# LPF-400kHz-OPA820-THT.net
KiCad netlist of a schematic drawn in Altium Designer
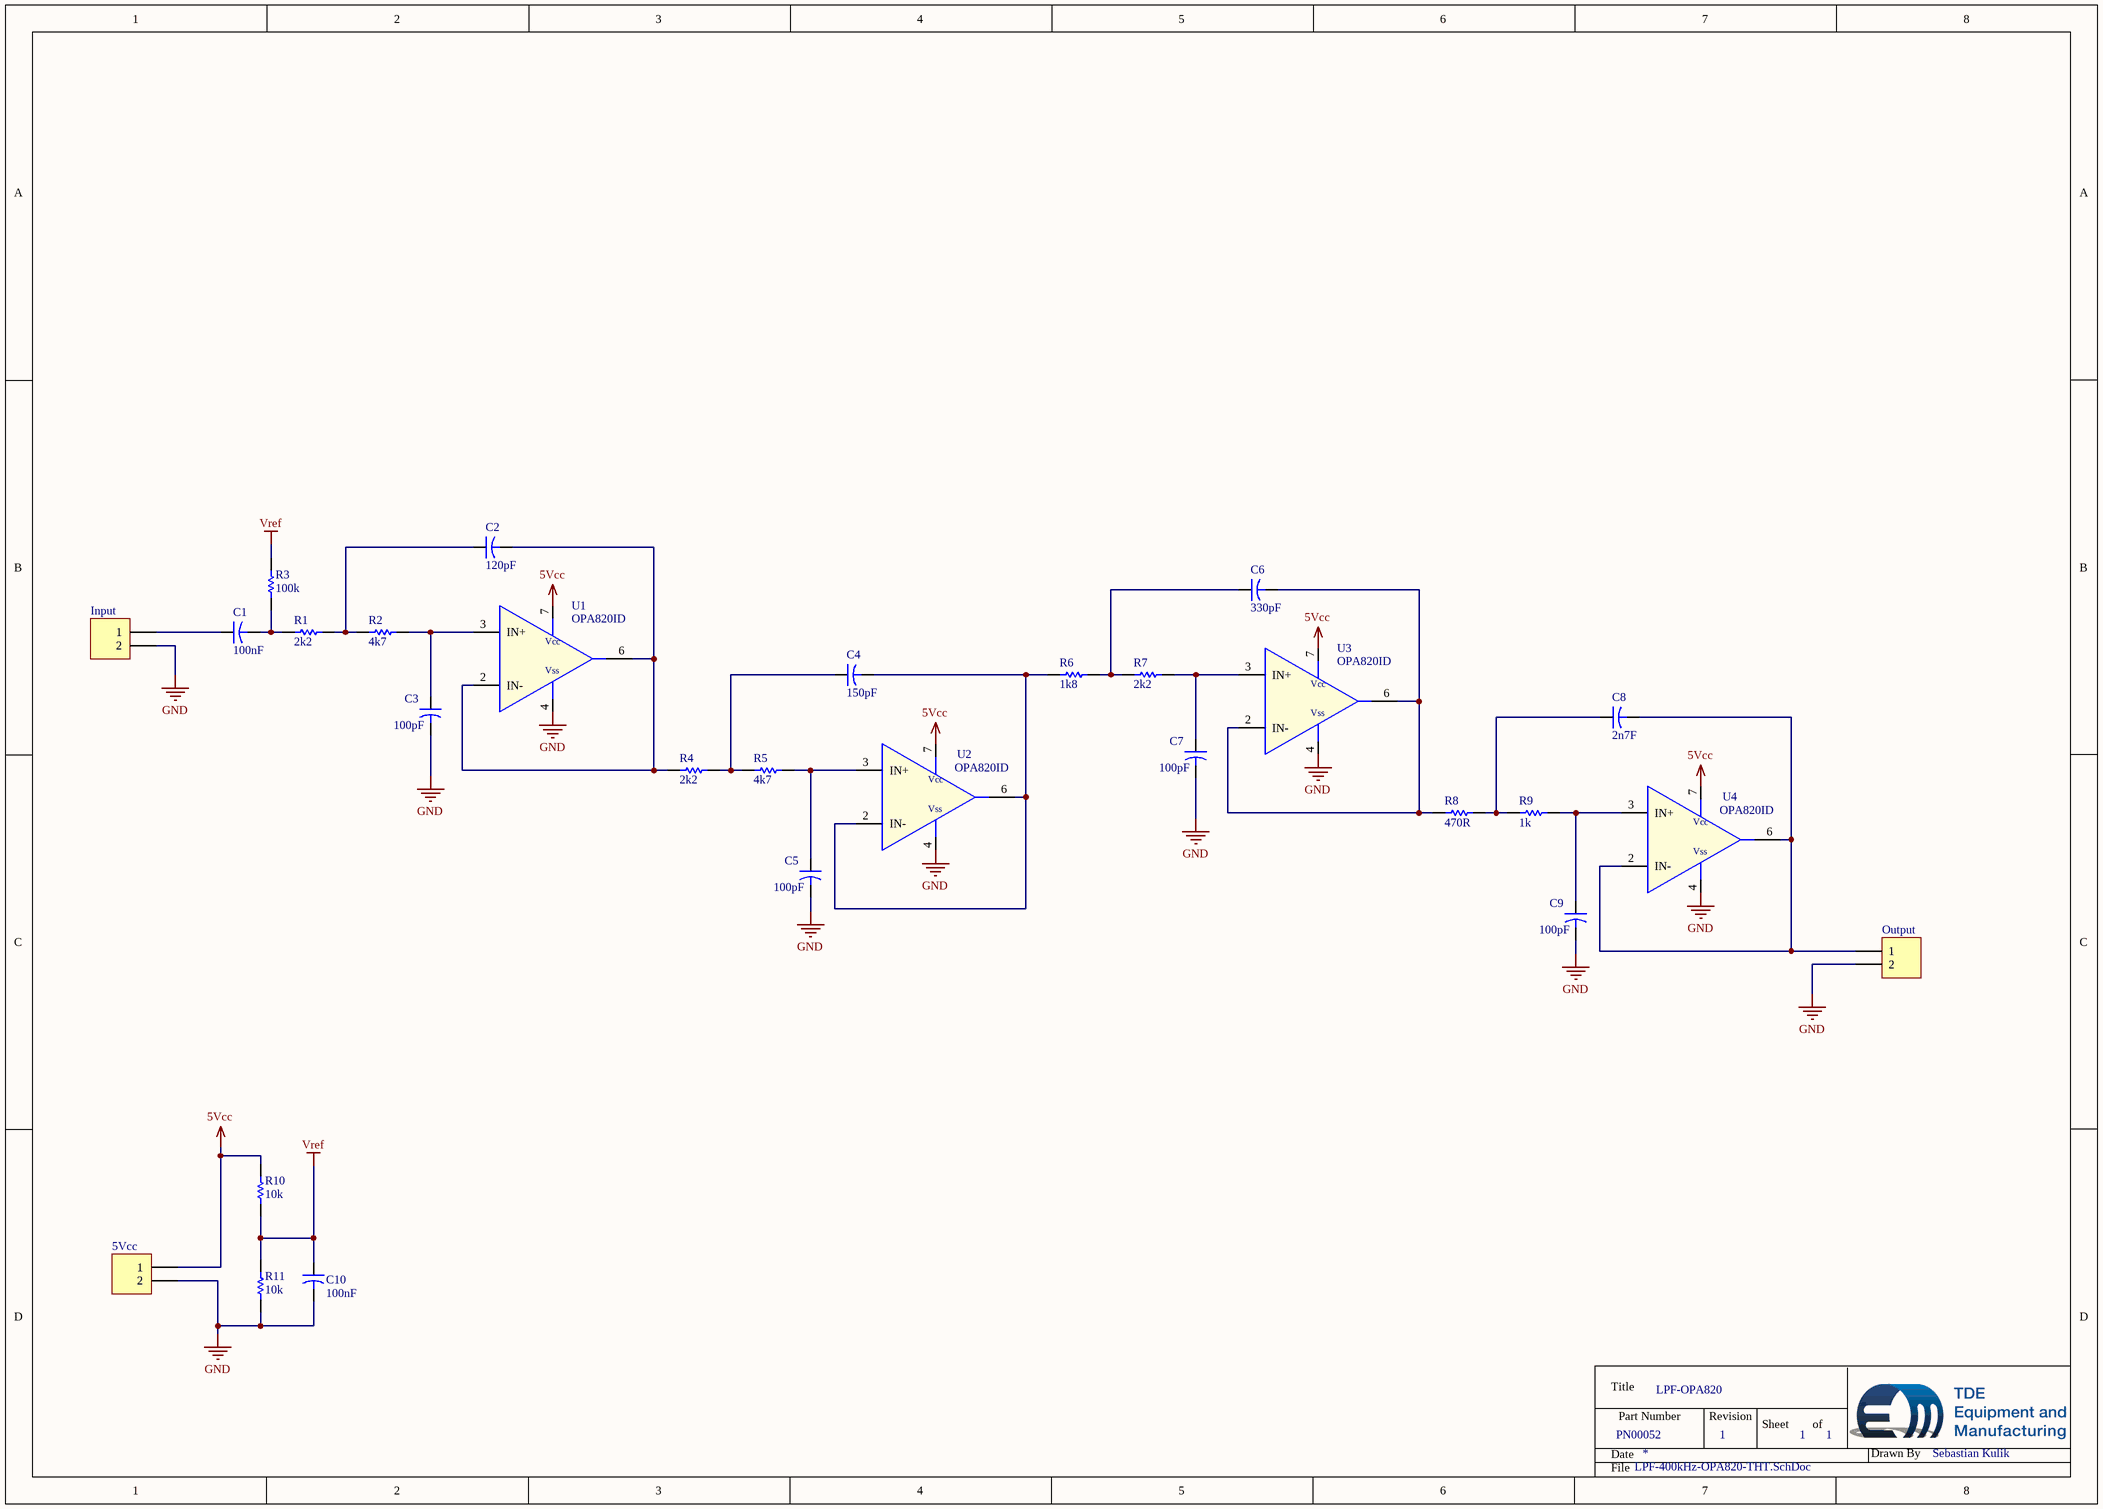
[diagram p0: LPF-400kHz-OPA820-THT.SchDoc]

(export (version "E")
  (design (tool "Eeschema 10.0.6"))
  (components
    (comp (ref "5Vcc")
      (value "PHOENIX_1715721")
      (footprint "Phoenix-2-5_08")
      (description "Phoenix, 2 pol, 5.08mm, 22A, 715721")
      (fields (field (name "MANUFACTURER") "Phoenix") (field (name "PUBLISHER") "Sebastian Kulik"))
      (libsource (lib "Connectors") (part "2Pol_1715721"))
    )
    (comp (ref "C1")
      (value "100nF")
      (footprint "Dummy-10mm")
      (description "Capacitor-Dummy-THT")
      (fields (field (name "PUBLISHER") "Sebastian Kulik"))
      (libsource (lib "Capacitors") (part "Capacitor-Dummy-THT"))
    )
    (comp (ref "C2")
      (value "120pF")
      (footprint "Dummy-10mm")
      (description "Capacitor-Dummy-THT")
      (fields (field (name "PUBLISHER") "Sebastian Kulik"))
      (libsource (lib "Capacitors") (part "Capacitor-Dummy-THT"))
    )
    (comp (ref "C3")
      (value "100pF")
      (footprint "Dummy-10mm")
      (description "Capacitor-Dummy-THT")
      (fields (field (name "PUBLISHER") "Sebastian Kulik"))
      (libsource (lib "Capacitors") (part "Capacitor-Dummy-THT"))
    )
    (comp (ref "C4")
      (value "150pF")
      (footprint "Dummy-10mm")
      (description "Capacitor-Dummy-THT")
      (fields (field (name "PUBLISHER") "Sebastian Kulik"))
      (libsource (lib "Capacitors") (part "Capacitor-Dummy-THT"))
    )
    (comp (ref "C5")
      (value "100pF")
      (footprint "Dummy-10mm")
      (description "Capacitor-Dummy-THT")
      (fields (field (name "PUBLISHER") "Sebastian Kulik"))
      (libsource (lib "Capacitors") (part "Capacitor-Dummy-THT"))
    )
    (comp (ref "C6")
      (value "330pF")
      (footprint "Dummy-10mm")
      (description "Capacitor-Dummy-THT")
      (fields (field (name "PUBLISHER") "Sebastian Kulik"))
      (libsource (lib "Capacitors") (part "Capacitor-Dummy-THT"))
    )
    (comp (ref "C7")
      (value "100pF")
      (footprint "Dummy-10mm")
      (description "Capacitor-Dummy-THT")
      (fields (field (name "PUBLISHER") "Sebastian Kulik"))
      (libsource (lib "Capacitors") (part "Capacitor-Dummy-THT"))
    )
    (comp (ref "C8")
      (value "2n7F")
      (footprint "Dummy-10mm")
      (description "Capacitor-Dummy-THT")
      (fields (field (name "PUBLISHER") "Sebastian Kulik"))
      (libsource (lib "Capacitors") (part "Capacitor-Dummy-THT"))
    )
    (comp (ref "C9")
      (value "100pF")
      (footprint "Dummy-10mm")
      (description "Capacitor-Dummy-THT")
      (fields (field (name "PUBLISHER") "Sebastian Kulik"))
      (libsource (lib "Capacitors") (part "Capacitor-Dummy-THT"))
    )
    (comp (ref "C10")
      (value "100nF")
      (footprint "Dummy-10mm")
      (description "Capacitor-Dummy-THT")
      (fields (field (name "PUBLISHER") "Sebastian Kulik"))
      (libsource (lib "Capacitors") (part "Capacitor-Dummy-THT"))
    )
    (comp (ref "Input")
      (value "PHOENIX_1715721")
      (footprint "Phoenix-2-5_08")
      (description "Phoenix, 2 pol, 5.08mm, 22A, 715721")
      (fields (field (name "MANUFACTURER") "Phoenix") (field (name "PUBLISHER") "Sebastian Kulik"))
      (libsource (lib "Connectors") (part "2Pol_1715721"))
    )
    (comp (ref "Output")
      (value "PHOENIX_1715721")
      (footprint "Phoenix-2-5_08")
      (description "Phoenix, 2 pol, 5.08mm, 22A, 715721")
      (fields (field (name "MANUFACTURER") "Phoenix") (field (name "PUBLISHER") "Sebastian Kulik"))
      (libsource (lib "") (part "2Pol_1715721_1"))
    )
    (comp (ref "R1")
      (value "2k2")
      (footprint "Dummy-10mm")
      (description "Resistor-Dummy-THT")
      (fields (field (name "PUBLISHER") "Sebastian Kulik"))
      (libsource (lib "Resistors") (part "Resistor-Dummy-THT"))
    )
    (comp (ref "R2")
      (value "4k7")
      (footprint "Dummy-10mm")
      (description "Resistor-Dummy-THT")
      (fields (field (name "PUBLISHER") "Sebastian Kulik"))
      (libsource (lib "Resistors") (part "Resistor-Dummy-THT"))
    )
    (comp (ref "R3")
      (value "100k")
      (footprint "Dummy-10mm")
      (description "Resistor-Dummy-THT")
      (fields (field (name "PUBLISHER") "Sebastian Kulik"))
      (libsource (lib "Resistors") (part "Resistor-Dummy-THT"))
    )
    (comp (ref "R4")
      (value "2k2")
      (footprint "Dummy-10mm")
      (description "Resistor-Dummy-THT")
      (fields (field (name "PUBLISHER") "Sebastian Kulik"))
      (libsource (lib "Resistors") (part "Resistor-Dummy-THT"))
    )
    (comp (ref "R5")
      (value "4k7")
      (footprint "Dummy-10mm")
      (description "Resistor-Dummy-THT")
      (fields (field (name "PUBLISHER") "Sebastian Kulik"))
      (libsource (lib "Resistors") (part "Resistor-Dummy-THT"))
    )
    (comp (ref "R6")
      (value "1k8")
      (footprint "Dummy-10mm")
      (description "Resistor-Dummy-THT")
      (fields (field (name "PUBLISHER") "Sebastian Kulik"))
      (libsource (lib "Resistors") (part "Resistor-Dummy-THT"))
    )
    (comp (ref "R7")
      (value "2k2")
      (footprint "Dummy-10mm")
      (description "Resistor-Dummy-THT")
      (fields (field (name "PUBLISHER") "Sebastian Kulik"))
      (libsource (lib "Resistors") (part "Resistor-Dummy-THT"))
    )
    (comp (ref "R8")
      (value "470R")
      (footprint "Dummy-10mm")
      (description "Resistor-Dummy-THT")
      (fields (field (name "PUBLISHER") "Sebastian Kulik"))
      (libsource (lib "Resistors") (part "Resistor-Dummy-THT"))
    )
    (comp (ref "R9")
      (value "1k")
      (footprint "Dummy-10mm")
      (description "Resistor-Dummy-THT")
      (fields (field (name "PUBLISHER") "Sebastian Kulik"))
      (libsource (lib "Resistors") (part "Resistor-Dummy-THT"))
    )
    (comp (ref "R10")
      (value "10k")
      (footprint "Dummy-10mm")
      (description "Resistor-Dummy-THT")
      (fields (field (name "PUBLISHER") "Sebastian Kulik"))
      (libsource (lib "Resistors") (part "Resistor-Dummy-THT"))
    )
    (comp (ref "R11")
      (value "10k")
      (footprint "Dummy-10mm")
      (description "Resistor-Dummy-THT")
      (fields (field (name "PUBLISHER") "Sebastian Kulik"))
      (libsource (lib "Resistors") (part "Resistor-Dummy-THT"))
    )
    (comp (ref "U1")
      (value "OPA820ID")
      (footprint "SOP8_L")
      (description "High speed OP, 260MHz")
      (fields (field (name "MANUFACTURER") "TI") (field (name "PUBLISHER") "Sebastian Kulik"))
      (libsource (lib "ICs") (part "OPA820ID"))
    )
    (comp (ref "U2")
      (value "OPA820ID")
      (footprint "SOP8_L")
      (description "High speed OP, 260MHz")
      (fields (field (name "MANUFACTURER") "TI") (field (name "PUBLISHER") "Sebastian Kulik"))
      (libsource (lib "ICs") (part "OPA820ID"))
    )
    (comp (ref "U3")
      (value "OPA820ID")
      (footprint "SOP8_L")
      (description "High speed OP, 260MHz")
      (fields (field (name "MANUFACTURER") "TI") (field (name "PUBLISHER") "Sebastian Kulik"))
      (libsource (lib "") (part "OPA820ID_2"))
    )
    (comp (ref "U4")
      (value "OPA820ID")
      (footprint "SOP8_L")
      (description "High speed OP, 260MHz")
      (fields (field (name "MANUFACTURER") "TI") (field (name "PUBLISHER") "Sebastian Kulik"))
      (libsource (lib "") (part "OPA820ID_1"))
    )
  )
  (nets
    (net (code "1") (name "5Vcc") (class "Default")
      (node (ref "5Vcc") (pin "1") (pinfunction "1_1") (pintype "passive"))
      (node (ref "R10") (pin "2") (pinfunction "2_2") (pintype "passive"))
      (node (ref "U1") (pin "7") (pinfunction "Vcc_7") (pintype "passive"))
      (node (ref "U2") (pin "7") (pinfunction "Vcc_7") (pintype "passive"))
      (node (ref "U3") (pin "7") (pinfunction "Vcc_7") (pintype "passive"))
      (node (ref "U4") (pin "7") (pinfunction "Vcc_7") (pintype "passive"))
    )
    (net (code "2") (name "GND") (class "Default")
      (node (ref "5Vcc") (pin "2") (pinfunction "2_2") (pintype "passive"))
      (node (ref "C10") (pin "2") (pinfunction "2_2") (pintype "passive"))
      (node (ref "C3") (pin "2") (pinfunction "2_2") (pintype "passive"))
      (node (ref "C5") (pin "2") (pinfunction "2_2") (pintype "passive"))
      (node (ref "C7") (pin "2") (pinfunction "2_2") (pintype "passive"))
      (node (ref "C9") (pin "2") (pinfunction "2_2") (pintype "passive"))
      (node (ref "Input") (pin "2") (pinfunction "2_2") (pintype "passive"))
      (node (ref "Output") (pin "2") (pinfunction "2_2") (pintype "passive"))
      (node (ref "R11") (pin "1") (pinfunction "1_1") (pintype "passive"))
      (node (ref "U1") (pin "4") (pinfunction "Vss_4") (pintype "passive"))
      (node (ref "U2") (pin "4") (pinfunction "Vss_4") (pintype "passive"))
      (node (ref "U3") (pin "4") (pinfunction "Vss_4") (pintype "passive"))
      (node (ref "U4") (pin "4") (pinfunction "Vss_4") (pintype "passive"))
    )
    (net (code "3") (name "Net-(C1-Pad1)") (class "Default")
      (node (ref "C1") (pin "1") (pinfunction "1_1") (pintype "passive"))
      (node (ref "Input") (pin "1") (pinfunction "1_1") (pintype "passive"))
    )
    (net (code "4") (name "Net-(C1-Pad2)") (class "Default")
      (node (ref "C1") (pin "2") (pinfunction "2_2") (pintype "passive"))
      (node (ref "R1") (pin "1") (pinfunction "1_1") (pintype "passive"))
      (node (ref "R3") (pin "1") (pinfunction "1_1") (pintype "passive"))
    )
    (net (code "5") (name "Net-(C2-Pad1)") (class "Default")
      (node (ref "C2") (pin "1") (pinfunction "1_1") (pintype "passive"))
      (node (ref "R1") (pin "2") (pinfunction "2_2") (pintype "passive"))
      (node (ref "R2") (pin "1") (pinfunction "1_1") (pintype "passive"))
    )
    (net (code "6") (name "Net-(C4-Pad1)") (class "Default")
      (node (ref "C4") (pin "1") (pinfunction "1_1") (pintype "passive"))
      (node (ref "R4") (pin "2") (pinfunction "2_2") (pintype "passive"))
      (node (ref "R5") (pin "1") (pinfunction "1_1") (pintype "passive"))
    )
    (net (code "7") (name "Net-(C6-Pad1)") (class "Default")
      (node (ref "C6") (pin "1") (pinfunction "1_1") (pintype "passive"))
      (node (ref "R6") (pin "2") (pinfunction "2_2") (pintype "passive"))
      (node (ref "R7") (pin "1") (pinfunction "1_1") (pintype "passive"))
    )
    (net (code "8") (name "Net-(C8-Pad1)") (class "Default")
      (node (ref "C8") (pin "1") (pinfunction "1_1") (pintype "passive"))
      (node (ref "R8") (pin "2") (pinfunction "2_2") (pintype "passive"))
      (node (ref "R9") (pin "1") (pinfunction "1_1") (pintype "passive"))
    )
    (net (code "9") (name "Net-(U1-IN+)") (class "Default")
      (node (ref "C3") (pin "1") (pinfunction "1_1") (pintype "passive"))
      (node (ref "R2") (pin "2") (pinfunction "2_2") (pintype "passive"))
      (node (ref "U1") (pin "3") (pinfunction "IN+_3") (pintype "power_in"))
    )
    (net (code "10") (name "Net-(U1-IN-)") (class "Default")
      (node (ref "C2") (pin "2") (pinfunction "2_2") (pintype "passive"))
      (node (ref "R4") (pin "1") (pinfunction "1_1") (pintype "passive"))
      (node (ref "U1") (pin "2") (pinfunction "IN-_2") (pintype "passive"))
      (node (ref "U1") (pin "6") (pinfunction "OUT_6") (pintype "passive"))
    )
    (net (code "11") (name "Net-(U2-IN+)") (class "Default")
      (node (ref "C5") (pin "1") (pinfunction "1_1") (pintype "passive"))
      (node (ref "R5") (pin "2") (pinfunction "2_2") (pintype "passive"))
      (node (ref "U2") (pin "3") (pinfunction "IN+_3") (pintype "power_in"))
    )
    (net (code "12") (name "Net-(U2-IN-)") (class "Default")
      (node (ref "C4") (pin "2") (pinfunction "2_2") (pintype "passive"))
      (node (ref "R6") (pin "1") (pinfunction "1_1") (pintype "passive"))
      (node (ref "U2") (pin "2") (pinfunction "IN-_2") (pintype "passive"))
      (node (ref "U2") (pin "6") (pinfunction "OUT_6") (pintype "passive"))
    )
    (net (code "13") (name "Net-(U3-IN+)") (class "Default")
      (node (ref "C7") (pin "1") (pinfunction "1_1") (pintype "passive"))
      (node (ref "R7") (pin "2") (pinfunction "2_2") (pintype "passive"))
      (node (ref "U3") (pin "3") (pinfunction "IN+_3") (pintype "power_in"))
    )
    (net (code "14") (name "Net-(U3-IN-)") (class "Default")
      (node (ref "C6") (pin "2") (pinfunction "2_2") (pintype "passive"))
      (node (ref "R8") (pin "1") (pinfunction "1_1") (pintype "passive"))
      (node (ref "U3") (pin "2") (pinfunction "IN-_2") (pintype "passive"))
      (node (ref "U3") (pin "6") (pinfunction "OUT_6") (pintype "passive"))
    )
    (net (code "15") (name "Net-(U4-IN+)") (class "Default")
      (node (ref "C9") (pin "1") (pinfunction "1_1") (pintype "passive"))
      (node (ref "R9") (pin "2") (pinfunction "2_2") (pintype "passive"))
      (node (ref "U4") (pin "3") (pinfunction "IN+_3") (pintype "power_in"))
    )
    (net (code "16") (name "Net-(U4-IN-)") (class "Default")
      (node (ref "C8") (pin "2") (pinfunction "2_2") (pintype "passive"))
      (node (ref "Output") (pin "1") (pinfunction "1_1") (pintype "passive"))
      (node (ref "U4") (pin "2") (pinfunction "IN-_2") (pintype "passive"))
      (node (ref "U4") (pin "6") (pinfunction "OUT_6") (pintype "passive"))
    )
    (net (code "17") (name "Vref") (class "Default")
      (node (ref "C10") (pin "1") (pinfunction "1_1") (pintype "passive"))
      (node (ref "R10") (pin "1") (pinfunction "1_1") (pintype "passive"))
      (node (ref "R11") (pin "2") (pinfunction "2_2") (pintype "passive"))
      (node (ref "R3") (pin "2") (pinfunction "2_2") (pintype "passive"))
    )
  )
)
